# amp_test.net
KiCad netlist of a schematic drawn in EAGLE
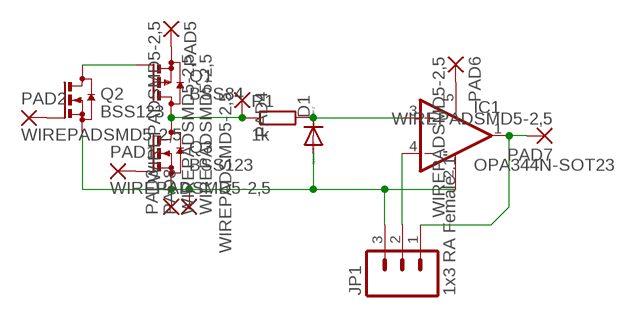
[diagram p0: schematic, sheet 1]

(export (version "E")
  (design (tool "Eeschema 10.0.6"))
  (components
    (comp (ref "D1")
      (value "DIODE-SOD323-R")
      (footprint "eagle-import:SOD323-R")
      (libsource (lib "eagle-import") (part "DIODE-SOD323-R"))
    )
    (comp (ref "IC1")
      (value "OPA344N-SOT23")
      (footprint "eagle-import:SOT23-5")
      (libsource (lib "eagle-import") (part "OPA-SOT23344N"))
    )
    (comp (ref "JP1")
      (value "1x3 RA Female .1\"")
      (footprint "eagle-import:1X03_SMD_RA_FEMALE")
      (libsource (lib "eagle-import") (part "M03SMD_RA_FEMALE"))
    )
    (comp (ref "PAD1")
      (value "WIREPADSMD5-2,5")
      (footprint "eagle-import:5-2,5")
      (libsource (lib "eagle-import") (part "WIREPADSMD5-2,5"))
    )
    (comp (ref "PAD2")
      (value "WIREPADSMD5-2,5")
      (footprint "eagle-import:5-2,5")
      (libsource (lib "eagle-import") (part "WIREPADSMD5-2,5"))
    )
    (comp (ref "PAD3")
      (value "WIREPADSMD5-2,5")
      (footprint "eagle-import:5-2,5")
      (libsource (lib "eagle-import") (part "WIREPADSMD5-2,5"))
    )
    (comp (ref "PAD4")
      (value "WIREPADSMD5-2,5")
      (footprint "eagle-import:5-2,5")
      (libsource (lib "eagle-import") (part "WIREPADSMD5-2,5"))
    )
    (comp (ref "PAD5")
      (value "WIREPADSMD5-2,5")
      (footprint "eagle-import:5-2,5")
      (libsource (lib "eagle-import") (part "WIREPADSMD5-2,5"))
    )
    (comp (ref "PAD6")
      (value "WIREPADSMD5-2,5")
      (footprint "eagle-import:5-2,5")
      (libsource (lib "eagle-import") (part "WIREPADSMD5-2,5"))
    )
    (comp (ref "PAD7")
      (value "WIREPADSMD5-2,5")
      (footprint "eagle-import:5-2,5")
      (libsource (lib "eagle-import") (part "WIREPADSMD5-2,5"))
    )
    (comp (ref "PAD8")
      (value "WIREPADSMD5-2,5")
      (footprint "eagle-import:5-2,5")
      (libsource (lib "eagle-import") (part "WIREPADSMD5-2,5"))
    )
    (comp (ref "Q1")
      (value "BSS84")
      (footprint "eagle-import:SOT23")
      (libsource (lib "eagle-import") (part "BSS84"))
    )
    (comp (ref "Q2")
      (value "BSS123")
      (footprint "eagle-import:SOT23")
      (libsource (lib "eagle-import") (part "BSS123"))
    )
    (comp (ref "Q3")
      (value "BSS123")
      (footprint "eagle-import:SOT23")
      (libsource (lib "eagle-import") (part "BSS123"))
    )
    (comp (ref "R1")
      (value "1k")
      (footprint "eagle-import:R0603")
      (libsource (lib "eagle-import") (part "R-EU_R0603"))
    )
  )
  (nets
    (net (code "1") (name "Net-(IC1-+IN)") (class "Default")
      (node (ref "D1") (pin "C") (pinfunction "C_C") (pintype "passive"))
      (node (ref "IC1") (pin "3") (pinfunction "+IN_3") (pintype "input"))
      (node (ref "R1") (pin "2") (pinfunction "2_2") (pintype "passive"))
    )
    (net (code "2") (name "Net-(IC1--IN)") (class "Default")
      (node (ref "IC1") (pin "4") (pinfunction "-IN_4") (pintype "input"))
      (node (ref "JP1") (pin "2") (pinfunction "2_2") (pintype "passive"))
    )
    (net (code "3") (name "Net-(IC1-OUT)") (class "Default")
      (node (ref "IC1") (pin "1") (pinfunction "OUT_1") (pintype "output"))
      (node (ref "JP1") (pin "1") (pinfunction "1_1") (pintype "passive"))
      (node (ref "PAD7") (pin "1") (pinfunction "P_1") (pintype "passive"))
    )
    (net (code "4") (name "Net-(IC1-V+)") (class "Default")
      (node (ref "IC1") (pin "5") (pinfunction "V+_5") (pintype "power_in"))
      (node (ref "PAD6") (pin "1") (pinfunction "P_1") (pintype "passive"))
    )
    (net (code "5") (name "Net-(IC1-V-)") (class "Default")
      (node (ref "D1") (pin "A") (pinfunction "A_A") (pintype "passive"))
      (node (ref "IC1") (pin "2") (pinfunction "V-_2") (pintype "power_in"))
      (node (ref "JP1") (pin "3") (pinfunction "3_3") (pintype "passive"))
      (node (ref "PAD3") (pin "1") (pinfunction "P_1") (pintype "passive"))
      (node (ref "PAD8") (pin "1") (pinfunction "P_1") (pintype "passive"))
      (node (ref "Q2") (pin "2") (pinfunction "S_2") (pintype "passive"))
      (node (ref "Q3") (pin "2") (pinfunction "S_2") (pintype "passive"))
    )
    (net (code "6") (name "Net-(PAD1-P)") (class "Default")
      (node (ref "PAD1") (pin "1") (pinfunction "P_1") (pintype "passive"))
      (node (ref "Q3") (pin "1") (pinfunction "G_1") (pintype "passive"))
    )
    (net (code "7") (name "Net-(PAD2-P)") (class "Default")
      (node (ref "PAD2") (pin "1") (pinfunction "P_1") (pintype "passive"))
      (node (ref "Q2") (pin "1") (pinfunction "G_1") (pintype "passive"))
    )
    (net (code "8") (name "Net-(PAD4-P)") (class "Default")
      (node (ref "PAD4") (pin "1") (pinfunction "P_1") (pintype "passive"))
      (node (ref "Q1") (pin "3") (pinfunction "D_3") (pintype "passive"))
      (node (ref "Q3") (pin "3") (pinfunction "D_3") (pintype "passive"))
      (node (ref "R1") (pin "1") (pinfunction "1_1") (pintype "passive"))
    )
    (net (code "9") (name "Net-(PAD5-P)") (class "Default")
      (node (ref "PAD5") (pin "1") (pinfunction "P_1") (pintype "passive"))
      (node (ref "Q1") (pin "2") (pinfunction "S_2") (pintype "passive"))
    )
    (net (code "10") (name "Net-(Q1-G)") (class "Default")
      (node (ref "Q1") (pin "1") (pinfunction "G_1") (pintype "passive"))
      (node (ref "Q2") (pin "3") (pinfunction "D_3") (pintype "passive"))
    )
  )
)
